# sensor-fusion.net
KiCad netlist of a schematic drawn in EAGLE
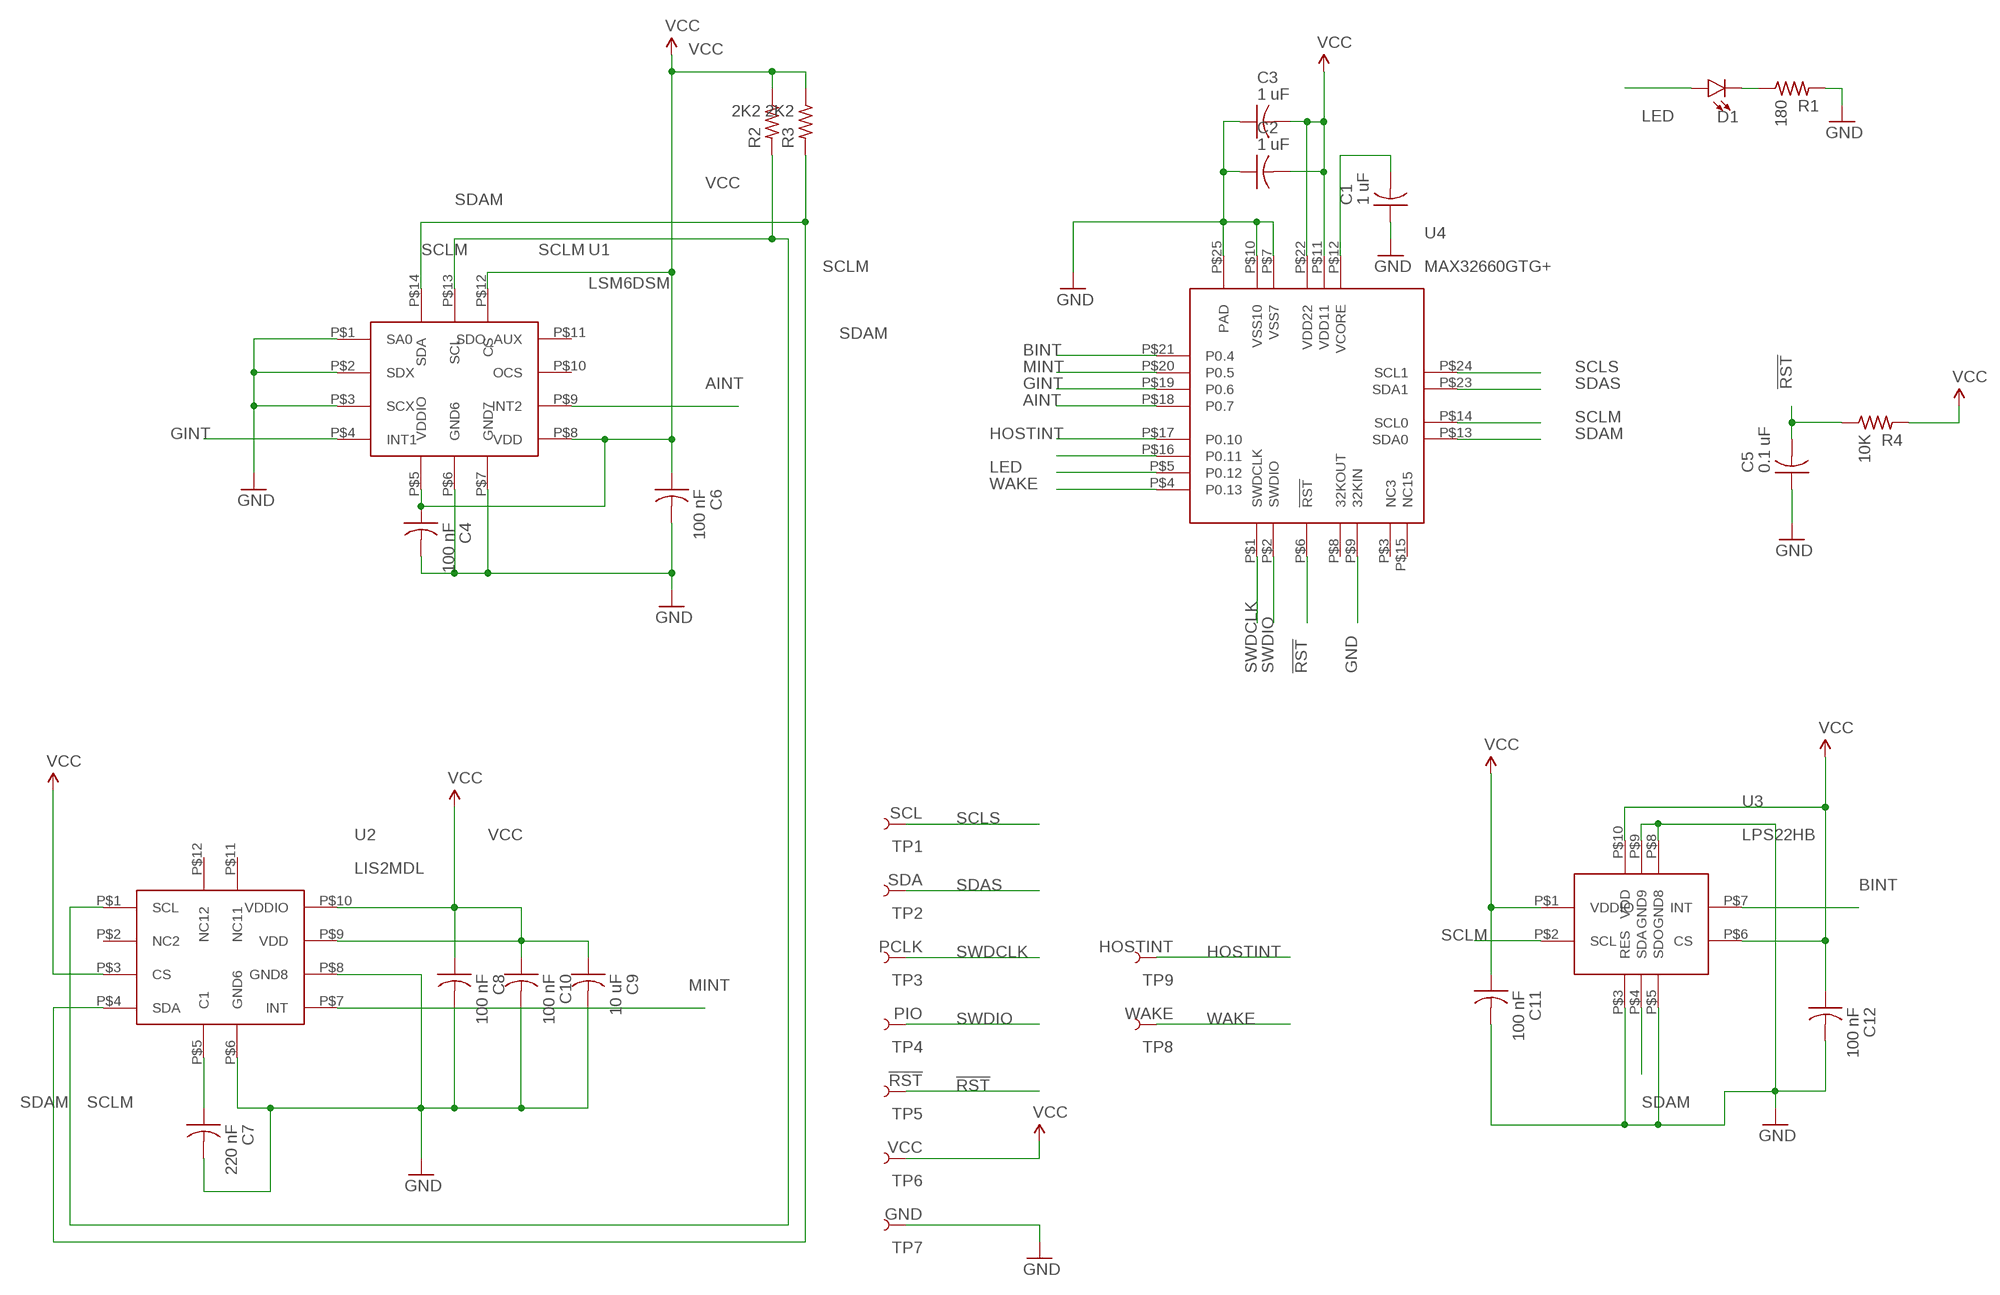
[diagram p0: schematic, sheet 1]

(export (version "E")
  (design (tool "Eeschema 10.0.6"))
  (components
    (comp (ref "C1")
      (value "1 uF")
      (footprint "eagle-import:C0402_B")
      (libsource (lib "eagle-import") (part "C-US"))
    )
    (comp (ref "C2")
      (value "1 uF")
      (footprint "eagle-import:C0402_B")
      (libsource (lib "eagle-import") (part "C-US"))
    )
    (comp (ref "C3")
      (value "1 uF")
      (footprint "eagle-import:C0402_B")
      (libsource (lib "eagle-import") (part "C-US"))
    )
    (comp (ref "C4")
      (value "100 nF")
      (footprint "eagle-import:C0402_B")
      (libsource (lib "eagle-import") (part "C-US"))
    )
    (comp (ref "C5")
      (value "0.1 uF")
      (footprint "eagle-import:C0402_B")
      (libsource (lib "eagle-import") (part "C-US"))
    )
    (comp (ref "C6")
      (value "100 nF")
      (footprint "eagle-import:C0402_B")
      (libsource (lib "eagle-import") (part "C-US"))
    )
    (comp (ref "C7")
      (value "220 nF")
      (footprint "eagle-import:C0402_B")
      (libsource (lib "eagle-import") (part "C-US"))
    )
    (comp (ref "C8")
      (value "100 nF")
      (footprint "eagle-import:C0402_B")
      (libsource (lib "eagle-import") (part "C-US"))
    )
    (comp (ref "C9")
      (value "10 uF")
      (footprint "eagle-import:C0402_B")
      (libsource (lib "eagle-import") (part "C-US"))
    )
    (comp (ref "C10")
      (value "100 nF")
      (footprint "eagle-import:C0402_B")
      (libsource (lib "eagle-import") (part "C-US"))
    )
    (comp (ref "C11")
      (value "100 nF")
      (footprint "eagle-import:C0402_B")
      (libsource (lib "eagle-import") (part "C-US"))
    )
    (comp (ref "C12")
      (value "100 nF")
      (footprint "eagle-import:C0402_B")
      (libsource (lib "eagle-import") (part "C-US"))
    )
    (comp (ref "D1")
      (value "LED0603")
      (footprint "eagle-import:LED-0603")
      (libsource (lib "eagle-import") (part "LED0603"))
    )
    (comp (ref "R1")
      (value "180")
      (footprint "eagle-import:R0402_B")
      (libsource (lib "eagle-import") (part "R-US_"))
    )
    (comp (ref "R2")
      (value "2K2")
      (footprint "eagle-import:R0402_B")
      (libsource (lib "eagle-import") (part "R-US_"))
    )
    (comp (ref "R3")
      (value "2K2")
      (footprint "eagle-import:R0402_B")
      (libsource (lib "eagle-import") (part "R-US_"))
    )
    (comp (ref "R4")
      (value "10K")
      (footprint "eagle-import:R0402_B")
      (libsource (lib "eagle-import") (part "R-US_"))
    )
    (comp (ref "TP1")
      (value "SCL")
      (footprint "eagle-import:PAD.03X.06")
      (libsource (lib "eagle-import") (part "TEST-POINT3X6"))
    )
    (comp (ref "TP2")
      (value "SDA")
      (footprint "eagle-import:PAD.03X.06")
      (libsource (lib "eagle-import") (part "TEST-POINT3X6"))
    )
    (comp (ref "TP3")
      (value "PCLK")
      (footprint "eagle-import:PAD.03X.06")
      (libsource (lib "eagle-import") (part "TEST-POINT3X6"))
    )
    (comp (ref "TP4")
      (value "PIO")
      (footprint "eagle-import:PAD.03X.06")
      (libsource (lib "eagle-import") (part "TEST-POINT3X6"))
    )
    (comp (ref "TP5")
      (value "!RST")
      (footprint "eagle-import:PAD.03X.06")
      (libsource (lib "eagle-import") (part "TEST-POINT3X6"))
    )
    (comp (ref "TP6")
      (value "VCC")
      (footprint "eagle-import:PAD.03X.06")
      (libsource (lib "eagle-import") (part "TEST-POINT3X6"))
    )
    (comp (ref "TP7")
      (value "GND")
      (footprint "eagle-import:PAD.03X.06")
      (libsource (lib "eagle-import") (part "TEST-POINT3X6"))
    )
    (comp (ref "TP8")
      (value "WAKE")
      (footprint "eagle-import:PAD.03X.06")
      (libsource (lib "eagle-import") (part "TEST-POINT3X6"))
    )
    (comp (ref "TP9")
      (value "HOSTINT")
      (footprint "eagle-import:PAD.03X.06")
      (libsource (lib "eagle-import") (part "TEST-POINT3X6"))
    )
    (comp (ref "U1")
      (value "LSM6DSM")
      (footprint "eagle-import:LSM6DSM")
      (libsource (lib "eagle-import") (part "LSM6DSM"))
    )
    (comp (ref "U2")
      (value "LIS2MDL")
      (footprint "eagle-import:LIS2MDL")
      (libsource (lib "eagle-import") (part "LIS2MDL"))
    )
    (comp (ref "U3")
      (value "LPS22HB")
      (footprint "eagle-import:LPS22HB")
      (libsource (lib "eagle-import") (part "LPS22HB"))
    )
    (comp (ref "U4")
      (value "MAX32660GTG+")
      (footprint "eagle-import:MAX32660GTG+")
      (libsource (lib "eagle-import") (part "MAX32660GTG+"))
    )
  )
  (nets
    (net (code "1") (name "/AINT") (class "Default")
      (node (ref "U1") (pin "P$9") (pinfunction "INT2_P$9") (pintype "bidirectional"))
      (node (ref "U4") (pin "P$18") (pinfunction "P0.7_P$18") (pintype "bidirectional"))
    )
    (net (code "2") (name "/BINT") (class "Default")
      (node (ref "U3") (pin "P$7") (pinfunction "INT_P$7") (pintype "bidirectional"))
      (node (ref "U4") (pin "P$21") (pinfunction "P0.4_P$21") (pintype "bidirectional"))
    )
    (net (code "3") (name "/GINT") (class "Default")
      (node (ref "U1") (pin "P$4") (pinfunction "INT1_P$4") (pintype "bidirectional"))
      (node (ref "U4") (pin "P$19") (pinfunction "P0.6_P$19") (pintype "bidirectional"))
    )
    (net (code "4") (name "/HOSTINT") (class "Default")
      (node (ref "TP9") (pin "1") (pinfunction "1_1") (pintype "bidirectional"))
      (node (ref "U4") (pin "P$17") (pinfunction "P0.10_P$17") (pintype "bidirectional"))
    )
    (net (code "5") (name "/LED") (class "Default")
      (node (ref "D1") (pin "A") (pinfunction "A_A") (pintype "passive"))
      (node (ref "U4") (pin "P$5") (pinfunction "P0.12_P$5") (pintype "bidirectional"))
    )
    (net (code "6") (name "/MINT") (class "Default")
      (node (ref "U2") (pin "P$7") (pinfunction "INT_P$7") (pintype "bidirectional"))
      (node (ref "U4") (pin "P$20") (pinfunction "P0.5_P$20") (pintype "bidirectional"))
    )
    (net (code "7") (name "/OCS") (class "Default")
      (node (ref "U1") (pin "P$10") (pinfunction "OCS_P$10") (pintype "power_in"))
    )
    (net (code "8") (name "/SCLM") (class "Default")
      (node (ref "R2") (pin "2") (pinfunction "2_2") (pintype "passive"))
      (node (ref "U1") (pin "P$13") (pinfunction "SCL_P$13") (pintype "bidirectional"))
      (node (ref "U2") (pin "P$1") (pinfunction "SCL_P$1") (pintype "bidirectional"))
      (node (ref "U3") (pin "P$2") (pinfunction "SCL_P$2") (pintype "bidirectional"))
      (node (ref "U4") (pin "P$14") (pinfunction "SCL0_P$14") (pintype "bidirectional"))
    )
    (net (code "9") (name "/SCLS") (class "Default")
      (node (ref "TP1") (pin "1") (pinfunction "1_1") (pintype "bidirectional"))
      (node (ref "U4") (pin "P$24") (pinfunction "SCL1_P$24") (pintype "bidirectional"))
    )
    (net (code "10") (name "/SDAM") (class "Default")
      (node (ref "R3") (pin "2") (pinfunction "2_2") (pintype "passive"))
      (node (ref "U1") (pin "P$14") (pinfunction "SDA_P$14") (pintype "bidirectional"))
      (node (ref "U2") (pin "P$4") (pinfunction "SDA_P$4") (pintype "bidirectional"))
      (node (ref "U3") (pin "P$4") (pinfunction "SDA_P$4") (pintype "bidirectional"))
      (node (ref "U4") (pin "P$13") (pinfunction "SDA0_P$13") (pintype "bidirectional"))
    )
    (net (code "11") (name "/SDAS") (class "Default")
      (node (ref "TP2") (pin "1") (pinfunction "1_1") (pintype "bidirectional"))
      (node (ref "U4") (pin "P$23") (pinfunction "SDA1_P$23") (pintype "bidirectional"))
    )
    (net (code "12") (name "/SDO_AUX") (class "Default")
      (node (ref "U1") (pin "P$11") (pinfunction "SDO_AUX_P$11") (pintype "power_in"))
    )
    (net (code "13") (name "/SWDCLK") (class "Default")
      (node (ref "TP3") (pin "1") (pinfunction "1_1") (pintype "bidirectional"))
      (node (ref "U4") (pin "P$1") (pinfunction "SWDCLK_P$1") (pintype "bidirectional"))
    )
    (net (code "14") (name "/SWDIO") (class "Default")
      (node (ref "TP4") (pin "1") (pinfunction "1_1") (pintype "bidirectional"))
      (node (ref "U4") (pin "P$2") (pinfunction "SWDIO_P$2") (pintype "bidirectional"))
    )
    (net (code "15") (name "/WAKE") (class "Default")
      (node (ref "TP8") (pin "1") (pinfunction "1_1") (pintype "bidirectional"))
      (node (ref "U4") (pin "P$4") (pinfunction "P0.13_P$4") (pintype "bidirectional"))
    )
    (net (code "16") (name "/~{RST}") (class "Default")
      (node (ref "C5") (pin "2") (pinfunction "2_2") (pintype "passive"))
      (node (ref "R4") (pin "1") (pinfunction "1_1") (pintype "passive"))
      (node (ref "TP5") (pin "1") (pinfunction "1_1") (pintype "bidirectional"))
      (node (ref "U4") (pin "P$6") (pinfunction "~{RST}_P$6") (pintype "bidirectional"))
    )
    (net (code "17") (name "GND") (class "Default")
      (node (ref "C1") (pin "1") (pinfunction "1_1") (pintype "passive"))
      (node (ref "C10") (pin "2") (pinfunction "2_2") (pintype "passive"))
      (node (ref "C11") (pin "2") (pinfunction "2_2") (pintype "passive"))
      (node (ref "C12") (pin "2") (pinfunction "2_2") (pintype "passive"))
      (node (ref "C2") (pin "1") (pinfunction "1_1") (pintype "passive"))
      (node (ref "C3") (pin "1") (pinfunction "1_1") (pintype "passive"))
      (node (ref "C4") (pin "2") (pinfunction "2_2") (pintype "passive"))
      (node (ref "C5") (pin "1") (pinfunction "1_1") (pintype "passive"))
      (node (ref "C6") (pin "2") (pinfunction "2_2") (pintype "passive"))
      (node (ref "C7") (pin "2") (pinfunction "2_2") (pintype "passive"))
      (node (ref "C8") (pin "2") (pinfunction "2_2") (pintype "passive"))
      (node (ref "C9") (pin "2") (pinfunction "2_2") (pintype "passive"))
      (node (ref "R1") (pin "2") (pinfunction "2_2") (pintype "passive"))
      (node (ref "TP7") (pin "1") (pinfunction "1_1") (pintype "bidirectional"))
      (node (ref "U1") (pin "P$1") (pinfunction "SA0_P$1") (pintype "bidirectional"))
      (node (ref "U1") (pin "P$2") (pinfunction "SDX_P$2") (pintype "power_in"))
      (node (ref "U1") (pin "P$3") (pinfunction "SCX_P$3") (pintype "power_in"))
      (node (ref "U1") (pin "P$6") (pinfunction "GND6_P$6") (pintype "power_in"))
      (node (ref "U1") (pin "P$7") (pinfunction "GND7_P$7") (pintype "power_in"))
      (node (ref "U2") (pin "P$6") (pinfunction "GND6_P$6") (pintype "power_in"))
      (node (ref "U2") (pin "P$8") (pinfunction "GND8_P$8") (pintype "power_in"))
      (node (ref "U3") (pin "P$3") (pinfunction "RES_P$3") (pintype "bidirectional"))
      (node (ref "U3") (pin "P$5") (pinfunction "SDO_P$5") (pintype "bidirectional"))
      (node (ref "U3") (pin "P$8") (pinfunction "GND8_P$8") (pintype "power_in"))
      (node (ref "U3") (pin "P$9") (pinfunction "GND9_P$9") (pintype "power_in"))
      (node (ref "U4") (pin "P$10") (pinfunction "VSS10_P$10") (pintype "power_in"))
      (node (ref "U4") (pin "P$25") (pinfunction "PAD_P$25") (pintype "power_in"))
      (node (ref "U4") (pin "P$7") (pinfunction "VSS7_P$7") (pintype "power_in"))
      (node (ref "U4") (pin "P$9") (pinfunction "32KIN_P$9") (pintype "bidirectional"))
    )
    (net (code "18") (name "Net-(D1-PadC)") (class "Default")
      (node (ref "D1") (pin "C") (pinfunction "C_C") (pintype "passive"))
      (node (ref "R1") (pin "1") (pinfunction "1_1") (pintype "passive"))
    )
    (net (code "19") (name "Net-(U2-C1)") (class "Default")
      (node (ref "C7") (pin "1") (pinfunction "1_1") (pintype "passive"))
      (node (ref "U2") (pin "P$5") (pinfunction "C1_P$5") (pintype "power_in"))
    )
    (net (code "20") (name "Net-(U4-VCORE)") (class "Default")
      (node (ref "C1") (pin "2") (pinfunction "2_2") (pintype "passive"))
      (node (ref "U4") (pin "P$12") (pinfunction "VCORE_P$12") (pintype "power_in"))
    )
    (net (code "21") (name "VCC") (class "Default")
      (node (ref "C10") (pin "1") (pinfunction "1_1") (pintype "passive"))
      (node (ref "C11") (pin "1") (pinfunction "1_1") (pintype "passive"))
      (node (ref "C12") (pin "1") (pinfunction "1_1") (pintype "passive"))
      (node (ref "C2") (pin "2") (pinfunction "2_2") (pintype "passive"))
      (node (ref "C3") (pin "2") (pinfunction "2_2") (pintype "passive"))
      (node (ref "C4") (pin "1") (pinfunction "1_1") (pintype "passive"))
      (node (ref "C6") (pin "1") (pinfunction "1_1") (pintype "passive"))
      (node (ref "C8") (pin "1") (pinfunction "1_1") (pintype "passive"))
      (node (ref "C9") (pin "1") (pinfunction "1_1") (pintype "passive"))
      (node (ref "R2") (pin "1") (pinfunction "1_1") (pintype "passive"))
      (node (ref "R3") (pin "1") (pinfunction "1_1") (pintype "passive"))
      (node (ref "R4") (pin "2") (pinfunction "2_2") (pintype "passive"))
      (node (ref "TP6") (pin "1") (pinfunction "1_1") (pintype "bidirectional"))
      (node (ref "U1") (pin "P$12") (pinfunction "CS_P$12") (pintype "power_in"))
      (node (ref "U1") (pin "P$5") (pinfunction "VDDIO_P$5") (pintype "power_in"))
      (node (ref "U1") (pin "P$8") (pinfunction "VDD_P$8") (pintype "power_in"))
      (node (ref "U2") (pin "P$10") (pinfunction "VDDIO_P$10") (pintype "power_in"))
      (node (ref "U2") (pin "P$3") (pinfunction "CS_P$3") (pintype "bidirectional"))
      (node (ref "U2") (pin "P$9") (pinfunction "VDD_P$9") (pintype "power_in"))
      (node (ref "U3") (pin "P$1") (pinfunction "VDDIO_P$1") (pintype "power_in"))
      (node (ref "U3") (pin "P$10") (pinfunction "VDD_P$10") (pintype "power_in"))
      (node (ref "U3") (pin "P$6") (pinfunction "CS_P$6") (pintype "bidirectional"))
      (node (ref "U4") (pin "P$11") (pinfunction "VDD11_P$11") (pintype "power_in"))
      (node (ref "U4") (pin "P$22") (pinfunction "VDD22_P$22") (pintype "power_in"))
    )
    (net (code "22") (name "unconnected-(U2-NC2-PadP$2)") (class "Default")
      (node (ref "U2") (pin "P$2") (pinfunction "NC2_P$2") (pintype "no_connect"))
    )
    (net (code "23") (name "unconnected-(U2-NC11-PadP$11)") (class "Default")
      (node (ref "U2") (pin "P$11") (pinfunction "NC11_P$11") (pintype "no_connect"))
    )
    (net (code "24") (name "unconnected-(U2-NC12-PadP$12)") (class "Default")
      (node (ref "U2") (pin "P$12") (pinfunction "NC12_P$12") (pintype "no_connect"))
    )
    (net (code "25") (name "unconnected-(U4-32KOUT-PadP$8)") (class "Default")
      (node (ref "U4") (pin "P$8") (pinfunction "32KOUT_P$8") (pintype "bidirectional"))
    )
    (net (code "26") (name "unconnected-(U4-NC3-PadP$3)") (class "Default")
      (node (ref "U4") (pin "P$3") (pinfunction "NC3_P$3") (pintype "no_connect"))
    )
    (net (code "27") (name "unconnected-(U4-NC15-PadP$15)") (class "Default")
      (node (ref "U4") (pin "P$15") (pinfunction "NC15_P$15") (pintype "no_connect"))
    )
    (net (code "28") (name "unconnected-(U4-P0.11-PadP$16)") (class "Default")
      (node (ref "U4") (pin "P$16") (pinfunction "P0.11_P$16") (pintype "bidirectional"))
    )
  )
)
